# 03_Power.net
KiCad netlist of a schematic drawn in Altium Designer
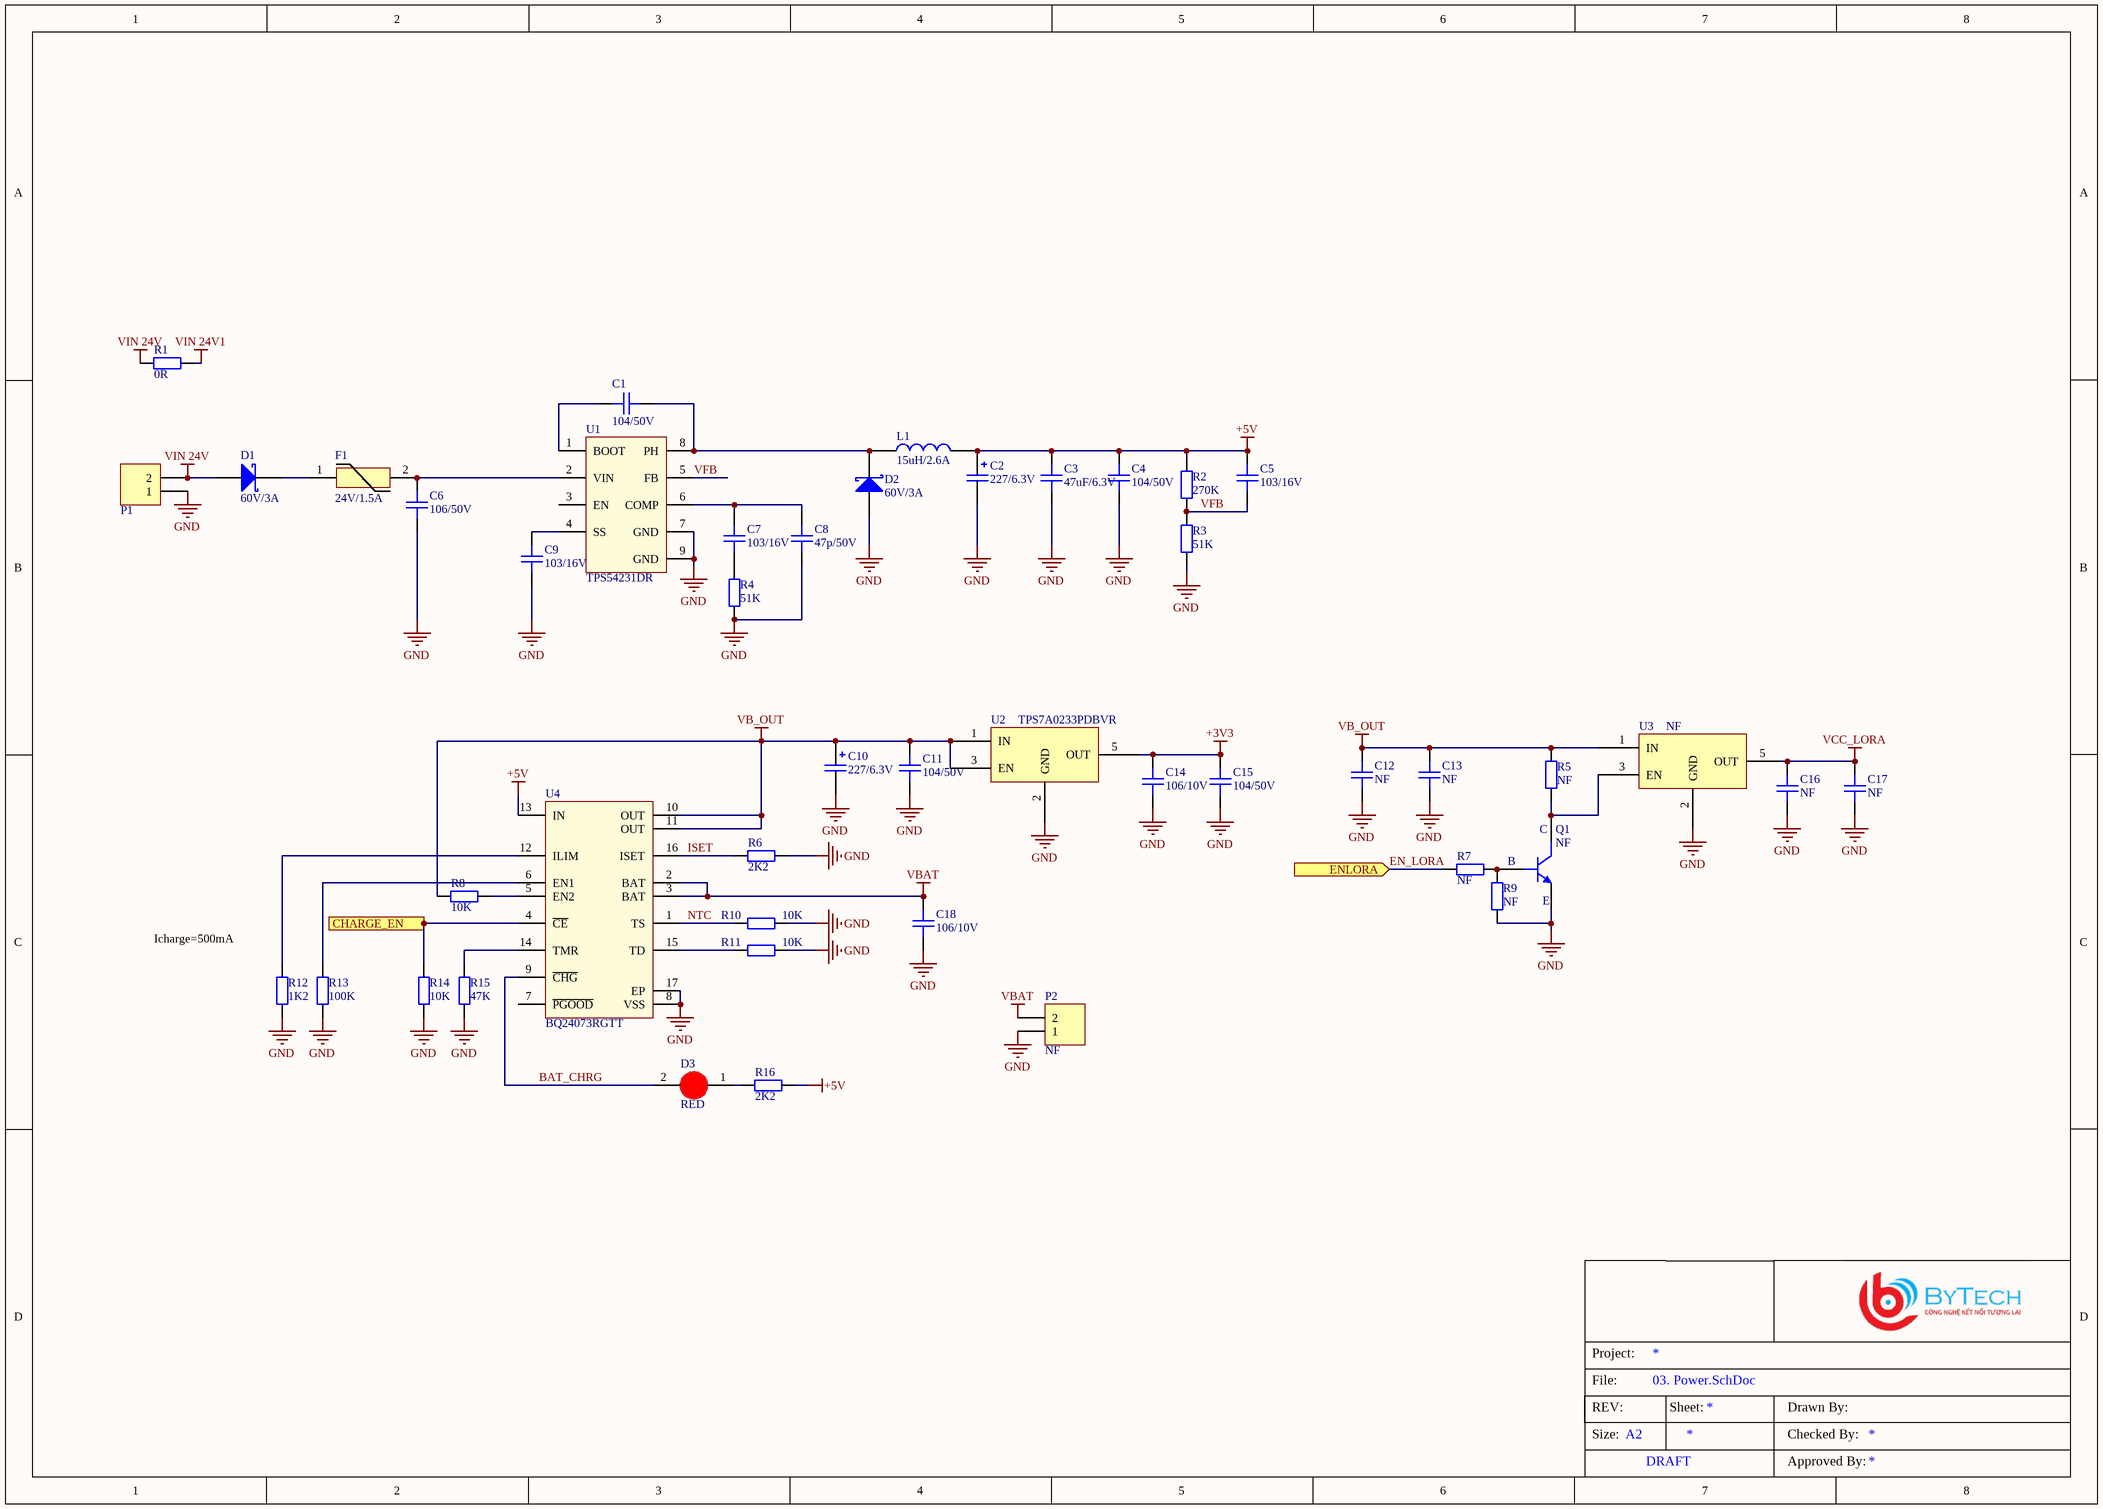
[diagram p0: 03. Power.SchDoc]

(export (version "E")
  (design (tool "Eeschema 10.0.6"))
  (components
    (comp (ref "C1")
      (value "104/50V")
      (footprint "CAPC-0603 (1608)")
      (description "CAP CER 0.1uF 50V 10% X7R 0603")
      (fields (field (name "MPN") "C0603C104K5RACTU"))
      (libsource (lib "01.Passives") (part "C0603C104K5RACTU"))
    )
    (comp (ref "C2")
      (value "227/6.3V")
      (footprint "CAP_TANTAL_1210(3528)")
      (description "CAP TANT POLY 220uF 20% 6.3V 3528 35mOhm ESR")
      (fields (field (name "MPN") "T520B227M006ATE035"))
      (libsource (lib "01.Passives") (part "T520B227M006ATE035"))
    )
    (comp (ref "C3")
      (value "47uF/6.3V")
      (footprint "CAPC-0603 (1608)")
      (description "CAP CER 47UF 6.3V X5R 0603")
      (fields (field (name "MPN") "GRM188R60J476ME15D") (field (name "MFR") "Murata Electronics"))
      (libsource (lib "01.Passives") (part "GRM188R60J476ME15D"))
    )
    (comp (ref "C4")
      (value "104/50V")
      (footprint "CAPC-0603 (1608)")
      (description "CAP CER 0.1uF 50V 10% X7R 0603")
      (fields (field (name "MPN") "C0603C104K5RACTU"))
      (libsource (lib "01.Passives") (part "C0603C104K5RACTU"))
    )
    (comp (ref "C5")
      (value "103/16V")
      (footprint "CAPC-0603 (1608)")
      (description "CAP CER 10nF 16V 10% X7R 0603")
      (fields (field (name "MPN") "CC0603KRX7R7BB103"))
      (libsource (lib "01.Passives") (part "CC0603KRX7R7BB103"))
    )
    (comp (ref "C6")
      (value "106/50V")
      (footprint "CAPC-1210 (3225)")
      (description "CAP CER 10uF 10% 50V X7R 1210 (3255)")
      (fields (field (name "MPN") "GRM32ER71H106KA12L"))
      (libsource (lib "01.Passives") (part "GRM32ER71H106KA12L"))
    )
    (comp (ref "C7")
      (value "103/16V")
      (footprint "CAPC-0603 (1608)")
      (description "CAP CER 10nF 16V 10% X7R 0603")
      (fields (field (name "MPN") "CC0603KRX7R7BB103"))
      (libsource (lib "01.Passives") (part "CC0603KRX7R7BB103"))
    )
    (comp (ref "C8")
      (value "47p/50V")
      (footprint "CAPC-0603 (1608)")
      (description "CAP CER 47pF 5% 50V C0G/NP0 0603")
      (fields (field (name "MPN") "CL10C470JB8NNNC"))
      (libsource (lib "01.Passives") (part "CL10C470JB8NNNC"))
    )
    (comp (ref "C9")
      (value "103/16V")
      (footprint "CAPC-0603 (1608)")
      (description "CAP CER 10nF 16V 10% X7R 0603")
      (fields (field (name "MPN") "CC0603KRX7R7BB103"))
      (libsource (lib "01.Passives") (part "CC0603KRX7R7BB103"))
    )
    (comp (ref "C10")
      (value "227/6.3V")
      (footprint "CAP_TANTAL_1210(3528)")
      (description "CAP TANT POLY 220uF 20% 6.3V 3528 35mOhm ESR")
      (fields (field (name "MPN") "T520B227M006ATE035"))
      (libsource (lib "01.Passives") (part "T520B227M006ATE035"))
    )
    (comp (ref "C11")
      (value "104/50V")
      (footprint "CAPC-0603 (1608)")
      (description "CAP CER 0.1uF 50V 10% X7R 0603")
      (fields (field (name "MPN") "C0603C104K5RACTU"))
      (libsource (lib "01.Passives") (part "C0603C104K5RACTU"))
    )
    (comp (ref "C12")
      (value "NF")
      (footprint "CAPC-0603 (1608)")
      (description "CAP CER 10uF 10% 10V X5R 0603")
      (fields (field (name "MPN") "CL10A106KP8NNNC"))
      (libsource (lib "01.Passives") (part "CL10A106KP8NNNC"))
    )
    (comp (ref "C13")
      (value "NF")
      (footprint "CAPC-0603 (1608)")
      (description "CAP CER 0.1uF 50V 10% X7R 0603")
      (fields (field (name "MPN") "C0603C104K5RACTU"))
      (libsource (lib "01.Passives") (part "C0603C104K5RACTU"))
    )
    (comp (ref "C14")
      (value "106/10V")
      (footprint "CAPC-0603 (1608)")
      (description "CAP CER 10uF 10% 10V X5R 0603")
      (fields (field (name "MPN") "CL10A106KP8NNNC"))
      (libsource (lib "01.Passives") (part "CL10A106KP8NNNC"))
    )
    (comp (ref "C15")
      (value "104/50V")
      (footprint "CAPC-0603 (1608)")
      (description "CAP CER 0.1uF 50V 10% X7R 0603")
      (fields (field (name "MPN") "C0603C104K5RACTU"))
      (libsource (lib "01.Passives") (part "C0603C104K5RACTU"))
    )
    (comp (ref "C16")
      (value "NF")
      (footprint "CAPC-0603 (1608)")
      (description "CAP CER 10uF 10% 10V X5R 0603")
      (fields (field (name "MPN") "CL10A106KP8NNNC"))
      (libsource (lib "01.Passives") (part "CL10A106KP8NNNC"))
    )
    (comp (ref "C17")
      (value "NF")
      (footprint "CAPC-0603 (1608)")
      (description "CAP CER 0.1uF 50V 10% X7R 0603")
      (fields (field (name "MPN") "C0603C104K5RACTU"))
      (libsource (lib "01.Passives") (part "C0603C104K5RACTU"))
    )
    (comp (ref "C18")
      (value "106/10V")
      (footprint "CAPC-0603 (1608)")
      (description "CAP CER 10uF 10% 10V X5R 0603")
      (fields (field (name "MPN") "CL10A106KP8NNNC"))
      (libsource (lib "01.Passives") (part "CL10A106KP8NNNC"))
    )
    (comp (ref "D1")
      (value "60V/3A")
      (footprint "DIODE_DO214AC_SMA")
      (description "DIODE SCHOTTKY 60V 3A DO214AC")
      (fields (field (name "MPN") "SK36A-LTP"))
      (libsource (lib "03.Semiconductor") (part "SK36A-LTP"))
    )
    (comp (ref "D2")
      (value "60V/3A")
      (footprint "DIODE_DO214AC_SMA")
      (description "DIODE SCHOTTKY 60V 3A DO214AC")
      (fields (field (name "MPN") "SK36A-LTP") (field (name "MANUFACTURER") "Micro Commercial Co"))
      (libsource (lib "03.Semiconductor") (part "SK36A-LTP"))
    )
    (comp (ref "D3")
      (value "RED")
      (footprint "LED 0603")
      (description "LED 0603 RED")
      (libsource (lib "03.Semiconductor") (part "LED 0603 RED"))
    )
    (comp (ref "F1")
      (value "24V/1.5A")
      (footprint "FUSE_1812(4532)")
      (description "FUSE PTC RESETTABLE 24V 1.50A 1812L")
      (fields (field (name "MPN") "1812L150/24MR"))
      (libsource (lib "02.Power,Protection") (part "1812L150/24MR"))
    )
    (comp (ref "L1")
      (value "15uH/2.6A")
      (footprint "IND-74404084150")
      (description "FIXED IND 15UH 2.6A 47 MOHM SMD")
      (fields (field (name "MPN") "74404084150") (field (name "MFR") "Würth Elektronik"))
      (libsource (lib "01.Passives") (part "74404084150"))
    )
    (comp (ref "P1")
      (value "15EDG3.81-2P")
      (footprint "HDR_3.81MM_RA_2x1")
      (description "Pluggable terminal 15EDG- 2P 3.81MM")
      (fields (field (name "MFR") "China"))
      (libsource (lib "04.Header-Connecter") (part "15EDG3.81-2P"))
    )
    (comp (ref "P2")
      (value "NF")
      (footprint "XH2.54-2P")
      (description "XH2.54mmm - 2P 180 degree")
      (fields (field (name "MPN") "XH-2A"))
      (libsource (lib "04.Header-Connecter") (part "XH-2A"))
    )
    (comp (ref "Q1")
      (value "NF")
      (footprint "SOT23_3")
      (description "TRANS NPN 50V 0.15A SOT23-3")
      (fields (field (name "MPN") "2SC1815"))
      (libsource (lib "03.Semiconductor") (part "2SC1815"))
    )
    (comp (ref "R1")
      (value "0R")
      (footprint "RESC-0603 (1608)")
      (description "RES SMD 0 OHM 1% 1/10W 0603")
      (fields (field (name "MPN") "RC0603FR-070R"))
      (libsource (lib "01.Passives") (part "RC0603FR-070R"))
    )
    (comp (ref "R2")
      (value "270K")
      (footprint "RESC-0603 (1608)")
      (description "RES SMD 270K OHM 0.1% 1/10W 0603")
      (fields (field (name "MPN") "RT0603BRD07270KL"))
      (libsource (lib "01.Passives") (part "RT0603BRD07270KL"))
    )
    (comp (ref "R3")
      (value "51K")
      (footprint "RESC-0603 (1608)")
      (description "RES SMD 51K OHM 1% 1/10W 0603")
      (fields (field (name "MPN") "RC0603FR-0751KL") (field (name "MFR") "Yageo"))
      (libsource (lib "01.Passives") (part "RC0603FR-0751KL"))
    )
    (comp (ref "R4")
      (value "51K")
      (footprint "RESC-0603 (1608)")
      (description "RES SMD 51K OHM 1% 1/10W 0603")
      (fields (field (name "MPN") "RC0603FR-0751KL") (field (name "MFR") "Yageo"))
      (libsource (lib "01.Passives") (part "RC0603FR-0751KL"))
    )
    (comp (ref "R5")
      (value "NF")
      (footprint "RESC-0603 (1608)")
      (description "RES SMD 10K OHM 1% 1/10W 0603")
      (fields (field (name "MPN") "RC0603FR-0710KL"))
      (libsource (lib "") (part "RC0603FR-0710KL_1"))
    )
    (comp (ref "R6")
      (value "2K2")
      (footprint "RESC-0603 (1608)")
      (description "RES SMD 2.2K OHM 1% 1/10W 0603")
      (fields (field (name "MPN") "CRCW06032K20FKEA"))
      (libsource (lib "01.Passives") (part "CRCW06032K20FKEA"))
    )
    (comp (ref "R7")
      (value "NF")
      (footprint "RESC-0603 (1608)")
      (description "RES SMD 1 KOHM 1% 1/10W 0603")
      (fields (field (name "MPN") "RC0603FR-071KL"))
      (libsource (lib "01.Passives") (part "RC0603FR-071KL"))
    )
    (comp (ref "R8")
      (value "10K")
      (footprint "RESC-0603 (1608)")
      (description "RES SMD 10K OHM 1% 1/10W 0603")
      (fields (field (name "MPN") "RC0603FR-0710KL"))
      (libsource (lib "01.Passives") (part "RC0603FR-0710KL"))
    )
    (comp (ref "R9")
      (value "NF")
      (footprint "RESC-0603 (1608)")
      (description "RES SMD 10K OHM 1% 1/10W 0603")
      (fields (field (name "MPN") "RC0603FR-0710KL"))
      (libsource (lib "") (part "RC0603FR-0710KL_1"))
    )
    (comp (ref "R10")
      (value "10K")
      (footprint "RESC-0603 (1608)")
      (description "RES SMD 10K OHM 1% 1/10W 0603")
      (fields (field (name "MPN") "RC0603FR-0710KL"))
      (libsource (lib "01.Passives") (part "RC0603FR-0710KL"))
    )
    (comp (ref "R11")
      (value "10K")
      (footprint "RESC-0603 (1608)")
      (description "RES SMD 10K OHM 1% 1/10W 0603")
      (fields (field (name "MPN") "RC0603FR-0710KL"))
      (libsource (lib "01.Passives") (part "RC0603FR-0710KL"))
    )
    (comp (ref "R12")
      (value "1K2")
      (footprint "RESC-0603 (1608)")
      (description "RES SMD 1.2K OHM 1% 1/10W 0603")
      (fields (field (name "MPN") "RC0603FR-071K2L"))
      (libsource (lib "01.Passives") (part "RC0603FR-071K2L"))
    )
    (comp (ref "R13")
      (value "100K")
      (footprint "RESC-0603 (1608)")
      (description "RES SMD 100K OHM 1% 1/10W 0603")
      (fields (field (name "MPN") "RC0603FR-07100KL"))
      (libsource (lib "01.Passives") (part "RC0603FR-07100KL"))
    )
    (comp (ref "R14")
      (value "10K")
      (footprint "RESC-0603 (1608)")
      (description "RES SMD 10K OHM 1% 1/10W 0603")
      (fields (field (name "MPN") "RC0603FR-0710KL"))
      (libsource (lib "") (part "RC0603FR-0710KL_1"))
    )
    (comp (ref "R15")
      (value "47K")
      (footprint "RESC-0603 (1608)")
      (description "RES SMD 47K OHM 1% 1/10W 0603")
      (fields (field (name "MPN") "RC0603FR0747KL"))
      (libsource (lib "01.Passives") (part "RC0603FR0747KL"))
    )
    (comp (ref "R16")
      (value "2K2")
      (footprint "RESC-0603 (1608)")
      (description "RES SMD 2.2K OHM 1% 1/10W 0603")
      (fields (field (name "MPN") "CRCW06032K20FKEA"))
      (libsource (lib "01.Passives") (part "CRCW06032K20FKEA"))
    )
    (comp (ref "U1")
      (value "TPS54231DR")
      (footprint "SOIC8 - TP")
      (description "IC REG BUCK ADJUSTABLE 2A 8SOIC")
      (fields (field (name "MFR") "TI"))
      (libsource (lib "05.IC") (part "TPS54231DR"))
    )
    (comp (ref "U2")
      (value "TPS7A0233PDBVR")
      (footprint "SOT23-5")
      (description "NANOPOWER LDO")
      (libsource (lib "05.IC") (part "TPS7A0233PDBVR"))
    )
    (comp (ref "U3")
      (value "NF")
      (footprint "SOT23-5")
      (description "NANOPOWER LDO")
      (fields (field (name "MPN") "TPS7A0233PDBVR"))
      (libsource (lib "05.IC") (part "TPS7A0233PDBVR"))
    )
    (comp (ref "U4")
      (value "BQ24073RGTT")
      (footprint "RGT16-1700X1700TP")
      (description "IC LI-ION CHARGE/PWR MGMT 16-QFN")
      (fields (field (name "MFR") "Texas Instruments"))
      (libsource (lib "05.IC") (part "BQ24073RGTT"))
    )
  )
  (nets
    (net (code "1") (name "+3V3") (class "Default")
      (node (ref "C14") (pin "2") (pinfunction "2_2") (pintype "passive"))
      (node (ref "C15") (pin "2") (pinfunction "2_2") (pintype "passive"))
      (node (ref "U2") (pin "5") (pinfunction "OUT_5") (pintype "passive"))
    )
    (net (code "2") (name "+5V") (class "Default")
      (node (ref "C2") (pin "1") (pinfunction "1_1") (pintype "passive"))
      (node (ref "C3") (pin "2") (pinfunction "2_2") (pintype "passive"))
      (node (ref "C4") (pin "2") (pinfunction "2_2") (pintype "passive"))
      (node (ref "C5") (pin "2") (pinfunction "2_2") (pintype "passive"))
      (node (ref "L1") (pin "2") (pinfunction "2_2") (pintype "passive"))
      (node (ref "R16") (pin "2") (pinfunction "2_2") (pintype "passive"))
      (node (ref "R2") (pin "2") (pinfunction "2_2") (pintype "passive"))
      (node (ref "U4") (pin "13") (pinfunction "IN_13") (pintype "power_in"))
    )
    (net (code "3") (name "/BAT_CHRG") (class "Default")
      (node (ref "D3") (pin "2") (pinfunction "K_2") (pintype "passive"))
      (node (ref "U4") (pin "9") (pinfunction "~{CHG}_9") (pintype "power_in"))
    )
    (net (code "4") (name "/CHARGE_EN") (class "Default")
      (node (ref "R14") (pin "2") (pinfunction "2_2") (pintype "passive"))
      (node (ref "U4") (pin "4") (pinfunction "~{CE}_4") (pintype "passive"))
    )
    (net (code "5") (name "/EN_LORA") (class "Default")
      (node (ref "R7") (pin "1") (pinfunction "1_1") (pintype "passive"))
    )
    (net (code "6") (name "/ISET") (class "Default")
      (node (ref "R6") (pin "1") (pinfunction "1_1") (pintype "passive"))
      (node (ref "U4") (pin "16") (pinfunction "ISET_16") (pintype "power_in"))
    )
    (net (code "7") (name "/NTC") (class "Default")
      (node (ref "R10") (pin "1") (pinfunction "1_1") (pintype "passive"))
      (node (ref "U4") (pin "1") (pinfunction "TS_1") (pintype "power_in"))
    )
    (net (code "8") (name "/VFB") (class "Default")
      (node (ref "C5") (pin "1") (pinfunction "1_1") (pintype "passive"))
      (node (ref "R2") (pin "1") (pinfunction "1_1") (pintype "passive"))
      (node (ref "R3") (pin "2") (pinfunction "2_2") (pintype "passive"))
      (node (ref "U1") (pin "5") (pinfunction "FB_5") (pintype "power_in"))
    )
    (net (code "9") (name "GND") (class "Default")
      (node (ref "C10") (pin "2") (pinfunction "2_2") (pintype "passive"))
      (node (ref "C11") (pin "1") (pinfunction "1_1") (pintype "passive"))
      (node (ref "C12") (pin "1") (pinfunction "1_1") (pintype "passive"))
      (node (ref "C13") (pin "1") (pinfunction "1_1") (pintype "passive"))
      (node (ref "C14") (pin "1") (pinfunction "1_1") (pintype "passive"))
      (node (ref "C15") (pin "1") (pinfunction "1_1") (pintype "passive"))
      (node (ref "C16") (pin "1") (pinfunction "1_1") (pintype "passive"))
      (node (ref "C17") (pin "1") (pinfunction "1_1") (pintype "passive"))
      (node (ref "C18") (pin "1") (pinfunction "1_1") (pintype "passive"))
      (node (ref "C2") (pin "2") (pinfunction "2_2") (pintype "passive"))
      (node (ref "C3") (pin "1") (pinfunction "1_1") (pintype "passive"))
      (node (ref "C4") (pin "1") (pinfunction "1_1") (pintype "passive"))
      (node (ref "C6") (pin "1") (pinfunction "1_1") (pintype "passive"))
      (node (ref "C8") (pin "1") (pinfunction "1_1") (pintype "passive"))
      (node (ref "C9") (pin "2") (pinfunction "2_2") (pintype "passive"))
      (node (ref "D2") (pin "1") (pinfunction "A_1") (pintype "passive"))
      (node (ref "P1") (pin "1") (pinfunction "1_1") (pintype "passive"))
      (node (ref "P2") (pin "1") (pinfunction "1_1") (pintype "passive"))
      (node (ref "Q1") (pin "2") (pinfunction "E_2") (pintype "passive"))
      (node (ref "R10") (pin "2") (pinfunction "2_2") (pintype "passive"))
      (node (ref "R11") (pin "2") (pinfunction "2_2") (pintype "passive"))
      (node (ref "R12") (pin "1") (pinfunction "1_1") (pintype "passive"))
      (node (ref "R13") (pin "1") (pinfunction "1_1") (pintype "passive"))
      (node (ref "R14") (pin "1") (pinfunction "1_1") (pintype "passive"))
      (node (ref "R15") (pin "1") (pinfunction "1_1") (pintype "passive"))
      (node (ref "R3") (pin "1") (pinfunction "1_1") (pintype "passive"))
      (node (ref "R4") (pin "1") (pinfunction "1_1") (pintype "passive"))
      (node (ref "R6") (pin "2") (pinfunction "2_2") (pintype "passive"))
      (node (ref "R9") (pin "1") (pinfunction "1_1") (pintype "passive"))
      (node (ref "U1") (pin "7") (pinfunction "GND_7") (pintype "power_in"))
      (node (ref "U1") (pin "9") (pinfunction "GND_9") (pintype "power_in"))
      (node (ref "U2") (pin "2") (pinfunction "GND_2") (pintype "passive"))
      (node (ref "U3") (pin "2") (pinfunction "GND_2") (pintype "passive"))
      (node (ref "U4") (pin "17") (pinfunction "EP_17") (pintype "power_in"))
      (node (ref "U4") (pin "8") (pinfunction "VSS_8") (pintype "power_in"))
    )
    (net (code "10") (name "Net-(C7-Pad2)") (class "Default")
      (node (ref "C7") (pin "2") (pinfunction "2_2") (pintype "passive"))
      (node (ref "R4") (pin "2") (pinfunction "2_2") (pintype "passive"))
    )
    (net (code "11") (name "Net-(D1-K)") (class "Default")
      (node (ref "D1") (pin "2") (pinfunction "K_2") (pintype "passive"))
      (node (ref "F1") (pin "1") (pinfunction "1_1") (pintype "passive"))
    )
    (net (code "12") (name "Net-(D2-K)") (class "Default")
      (node (ref "C1") (pin "2") (pinfunction "2_2") (pintype "passive"))
      (node (ref "D2") (pin "2") (pinfunction "K_2") (pintype "passive"))
      (node (ref "L1") (pin "1") (pinfunction "1_1") (pintype "passive"))
      (node (ref "U1") (pin "8") (pinfunction "PH_8") (pintype "power_in"))
    )
    (net (code "13") (name "Net-(D3-A)") (class "Default")
      (node (ref "D3") (pin "1") (pinfunction "A_1") (pintype "passive"))
      (node (ref "R16") (pin "1") (pinfunction "1_1") (pintype "passive"))
    )
    (net (code "14") (name "Net-(Q1-B)") (class "Default")
      (node (ref "Q1") (pin "1") (pinfunction "B_1") (pintype "passive"))
      (node (ref "R7") (pin "2") (pinfunction "2_2") (pintype "passive"))
      (node (ref "R9") (pin "2") (pinfunction "2_2") (pintype "passive"))
    )
    (net (code "15") (name "Net-(Q1-C)") (class "Default")
      (node (ref "Q1") (pin "3") (pinfunction "C_3") (pintype "passive"))
      (node (ref "R5") (pin "1") (pinfunction "1_1") (pintype "passive"))
      (node (ref "U3") (pin "3") (pinfunction "EN_3") (pintype "passive"))
    )
    (net (code "16") (name "Net-(U1-BOOT)") (class "Default")
      (node (ref "C1") (pin "1") (pinfunction "1_1") (pintype "passive"))
      (node (ref "U1") (pin "1") (pinfunction "BOOT_1") (pintype "power_in"))
    )
    (net (code "17") (name "Net-(U1-COMP)") (class "Default")
      (node (ref "C7") (pin "1") (pinfunction "1_1") (pintype "passive"))
      (node (ref "C8") (pin "2") (pinfunction "2_2") (pintype "passive"))
      (node (ref "U1") (pin "6") (pinfunction "COMP_6") (pintype "power_in"))
    )
    (net (code "18") (name "Net-(U1-SS)") (class "Default")
      (node (ref "C9") (pin "1") (pinfunction "1_1") (pintype "passive"))
      (node (ref "U1") (pin "4") (pinfunction "SS_4") (pintype "power_in"))
    )
    (net (code "19") (name "Net-(U1-VIN)") (class "Default")
      (node (ref "C6") (pin "2") (pinfunction "2_2") (pintype "passive"))
      (node (ref "F1") (pin "2") (pinfunction "2_2") (pintype "passive"))
      (node (ref "U1") (pin "2") (pinfunction "VIN_2") (pintype "power_in"))
    )
    (net (code "20") (name "Net-(U4-EN1)") (class "Default")
      (node (ref "R13") (pin "2") (pinfunction "2_2") (pintype "passive"))
      (node (ref "U4") (pin "6") (pinfunction "EN1_6") (pintype "power_in"))
    )
    (net (code "21") (name "Net-(U4-EN2)") (class "Default")
      (node (ref "R8") (pin "2") (pinfunction "2_2") (pintype "passive"))
      (node (ref "U4") (pin "5") (pinfunction "EN2_5") (pintype "power_in"))
    )
    (net (code "22") (name "Net-(U4-ILIM)") (class "Default")
      (node (ref "R12") (pin "2") (pinfunction "2_2") (pintype "passive"))
      (node (ref "U4") (pin "12") (pinfunction "ILIM_12") (pintype "power_in"))
    )
    (net (code "23") (name "Net-(U4-TD)") (class "Default")
      (node (ref "R11") (pin "1") (pinfunction "1_1") (pintype "passive"))
      (node (ref "U4") (pin "15") (pinfunction "TD_15") (pintype "power_in"))
    )
    (net (code "24") (name "Net-(U4-TMR)") (class "Default")
      (node (ref "R15") (pin "2") (pinfunction "2_2") (pintype "passive"))
      (node (ref "U4") (pin "14") (pinfunction "TMR_14") (pintype "power_in"))
    )
    (net (code "25") (name "VBAT") (class "Default")
      (node (ref "C18") (pin "2") (pinfunction "2_2") (pintype "passive"))
      (node (ref "P2") (pin "2") (pinfunction "2_2") (pintype "passive"))
      (node (ref "U4") (pin "2") (pinfunction "BAT_2") (pintype "power_in"))
      (node (ref "U4") (pin "3") (pinfunction "BAT_3") (pintype "power_in"))
    )
    (net (code "26") (name "VB_OUT") (class "Default")
      (node (ref "C10") (pin "1") (pinfunction "1_1") (pintype "passive"))
      (node (ref "C11") (pin "2") (pinfunction "2_2") (pintype "passive"))
      (node (ref "C12") (pin "2") (pinfunction "2_2") (pintype "passive"))
      (node (ref "C13") (pin "2") (pinfunction "2_2") (pintype "passive"))
      (node (ref "R5") (pin "2") (pinfunction "2_2") (pintype "passive"))
      (node (ref "R8") (pin "1") (pinfunction "1_1") (pintype "passive"))
      (node (ref "U2") (pin "1") (pinfunction "IN_1") (pintype "passive"))
      (node (ref "U2") (pin "3") (pinfunction "EN_3") (pintype "passive"))
      (node (ref "U3") (pin "1") (pinfunction "IN_1") (pintype "passive"))
      (node (ref "U4") (pin "10") (pinfunction "OUT_10") (pintype "power_in"))
      (node (ref "U4") (pin "11") (pinfunction "OUT_11") (pintype "power_in"))
    )
    (net (code "27") (name "VCC_LORA") (class "Default")
      (node (ref "C16") (pin "2") (pinfunction "2_2") (pintype "passive"))
      (node (ref "C17") (pin "2") (pinfunction "2_2") (pintype "passive"))
      (node (ref "U3") (pin "5") (pinfunction "OUT_5") (pintype "passive"))
    )
    (net (code "28") (name "VIN 24V") (class "Default")
      (node (ref "D1") (pin "1") (pinfunction "A_1") (pintype "passive"))
      (node (ref "P1") (pin "2") (pinfunction "2_2") (pintype "passive"))
      (node (ref "R1") (pin "1") (pinfunction "1_1") (pintype "passive"))
    )
    (net (code "29") (name "VIN 24V1") (class "Default")
      (node (ref "R1") (pin "2") (pinfunction "2_2") (pintype "passive"))
    )
    (net (code "30") (name "unconnected-(U1-EN-Pad3)") (class "Default")
      (node (ref "U1") (pin "3") (pinfunction "EN_3") (pintype "power_in"))
    )
    (net (code "31") (name "unconnected-(U4-~{PGOOD}-Pad7)") (class "Default")
      (node (ref "U4") (pin "7") (pinfunction "~{PGOOD}_7") (pintype "power_in"))
    )
  )
)
